# ADXL362_BOB_v01.net
KiCad netlist of a schematic drawn in EAGLE
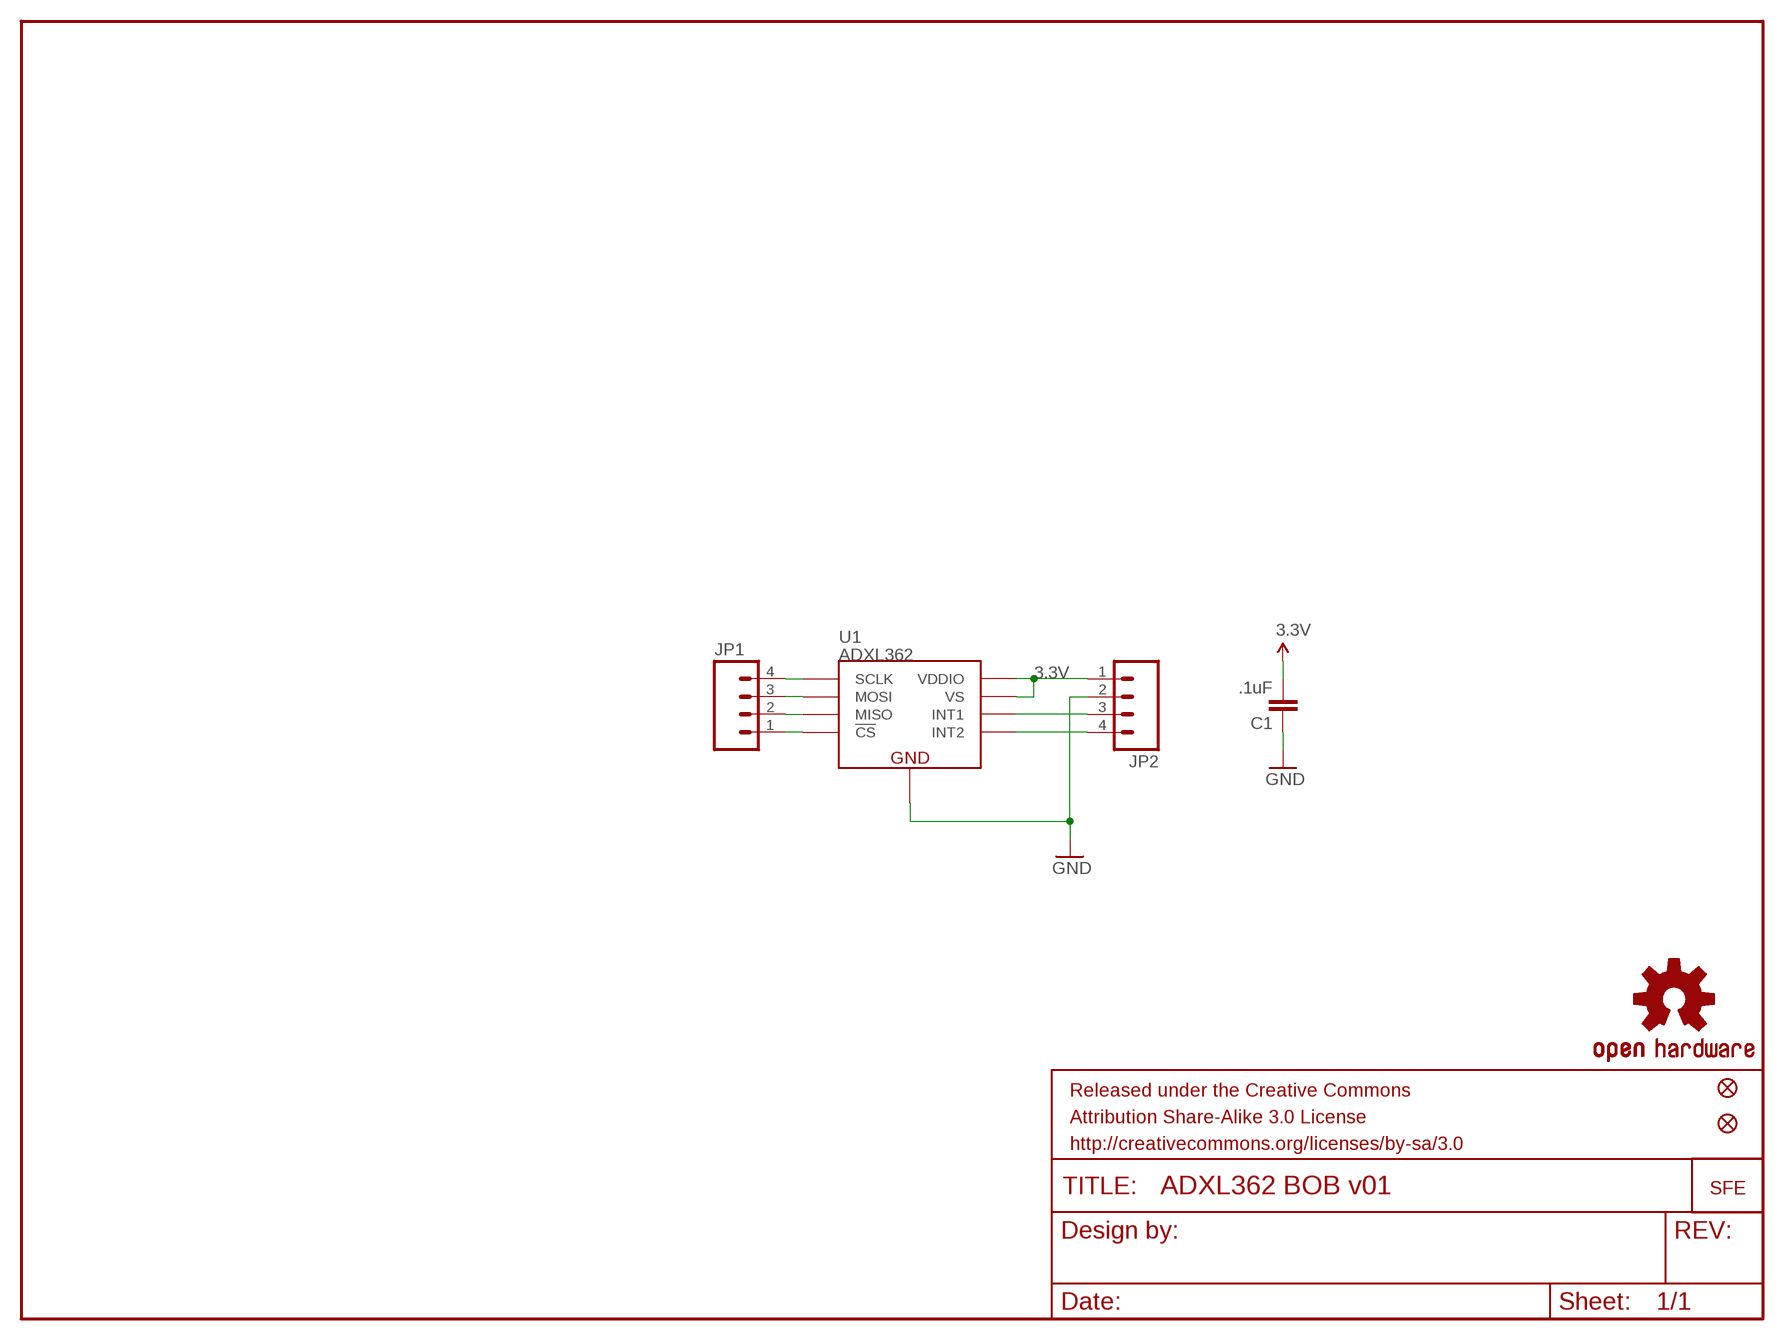
[diagram p0: schematic, sheet 1]

(export (version "E")
  (design (tool "Eeschema 10.0.6"))
  (components
    (comp (ref "C1")
      (value ".1uF")
      (footprint "eagle-import:0402-CAP")
      (libsource (lib "eagle-import") (part "CAP0402-CAP"))
    )
    (comp (ref "FRAME1")
      (value "FRAME-LETTER")
      (footprint "eagle-import:CREATIVE_COMMONS")
      (libsource (lib "eagle-import") (part "FRAME-LETTER"))
    )
    (comp (ref "JP1")
      (value "M04PTH")
      (footprint "eagle-import:1X04")
      (libsource (lib "eagle-import") (part "M04PTH"))
    )
    (comp (ref "JP2")
      (value "M04PTH")
      (footprint "eagle-import:1X04")
      (libsource (lib "eagle-import") (part "M04PTH"))
    )
    (comp (ref "JP3")
      (value "LOGO-SFESK")
      (footprint "eagle-import:SFE-LOGO-FLAME")
      (libsource (lib "eagle-import") (part "LOGO-SFESK"))
    )
    (comp (ref "JP4")
      (value "FIDUCIALUFIDUCIAL")
      (footprint "eagle-import:MICRO-FIDUCIAL")
      (libsource (lib "eagle-import") (part "FIDUCIALUFIDUCIAL"))
    )
    (comp (ref "JP5")
      (value "FIDUCIALUFIDUCIAL")
      (footprint "eagle-import:MICRO-FIDUCIAL")
      (libsource (lib "eagle-import") (part "FIDUCIALUFIDUCIAL"))
    )
    (comp (ref "U$1")
      (value "OSHW-LOGOS")
      (footprint "eagle-import:OSHW-LOGO-S")
      (libsource (lib "eagle-import") (part "OSHW-LOGOS"))
    )
    (comp (ref "U1")
      (value "ADXL362")
      (footprint "eagle-import:ADXL362")
      (libsource (lib "eagle-import") (part "ADXL362"))
    )
  )
  (nets
    (net (code "1") (name "3.3V") (class "Default")
      (node (ref "C1") (pin "2") (pinfunction "2_2") (pintype "passive"))
      (node (ref "JP2") (pin "1") (pinfunction "1_1") (pintype "passive"))
      (node (ref "U1") (pin "P$1") (pinfunction "VDDIO_P$1") (pintype "bidirectional"))
      (node (ref "U1") (pin "P$14") (pinfunction "VS_P$14") (pintype "bidirectional"))
    )
    (net (code "2") (name "GND") (class "Default")
      (node (ref "C1") (pin "1") (pinfunction "1_1") (pintype "passive"))
      (node (ref "JP2") (pin "2") (pinfunction "2_2") (pintype "passive"))
      (node (ref "U1") (pin "P$12") (pinfunction "GND_P$12") (pintype "bidirectional"))
      (node (ref "U1") (pin "P$13") (pinfunction "GND_P$13") (pintype "bidirectional"))
      (node (ref "U1") (pin "P$16") (pinfunction "GND_P$16") (pintype "bidirectional"))
    )
    (net (code "3") (name "Net-(U1-INT1)") (class "Default")
      (node (ref "JP2") (pin "3") (pinfunction "3_3") (pintype "passive"))
      (node (ref "U1") (pin "P$11") (pinfunction "INT1_P$11") (pintype "bidirectional"))
    )
    (net (code "4") (name "Net-(U1-INT2)") (class "Default")
      (node (ref "JP2") (pin "4") (pinfunction "4_4") (pintype "passive"))
      (node (ref "U1") (pin "P$9") (pinfunction "INT2_P$9") (pintype "bidirectional"))
    )
    (net (code "5") (name "Net-(U1-MISO)") (class "Default")
      (node (ref "JP1") (pin "2") (pinfunction "2_2") (pintype "passive"))
      (node (ref "U1") (pin "P$7") (pinfunction "MISO_P$7") (pintype "bidirectional"))
    )
    (net (code "6") (name "Net-(U1-MOSI)") (class "Default")
      (node (ref "JP1") (pin "3") (pinfunction "3_3") (pintype "passive"))
      (node (ref "U1") (pin "P$6") (pinfunction "MOSI_P$6") (pintype "bidirectional"))
    )
    (net (code "7") (name "Net-(U1-SCLK)") (class "Default")
      (node (ref "JP1") (pin "4") (pinfunction "4_4") (pintype "passive"))
      (node (ref "U1") (pin "P$4") (pinfunction "SCLK_P$4") (pintype "bidirectional"))
    )
    (net (code "8") (name "Net-(U1-~{CS})") (class "Default")
      (node (ref "JP1") (pin "1") (pinfunction "1_1") (pintype "passive"))
      (node (ref "U1") (pin "P$8") (pinfunction "~{CS}_P$8") (pintype "bidirectional"))
    )
  )
)
